# IRHapticFeedbackBoard.net
KiCad netlist of a schematic drawn in EAGLE
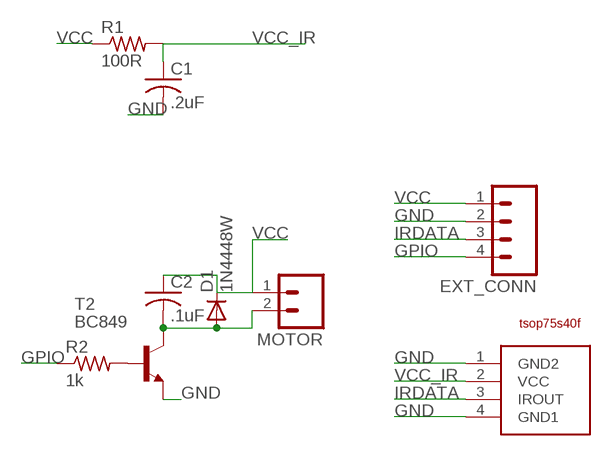
[diagram p0: schematic, sheet 1]

(export (version "E")
  (design (tool "Eeschema 10.0.6"))
  (components
    (comp (ref "C1")
      (value ".2uF")
      (footprint "eagle-import:C0603")
      (libsource (lib "eagle-import") (part "C-USC0603"))
    )
    (comp (ref "C2")
      (value ".1uF")
      (footprint "eagle-import:C0603")
      (libsource (lib "eagle-import") (part "C-USC0603"))
    )
    (comp (ref "D1")
      (value "1N4448W")
      (footprint "eagle-import:SOD-123")
      (libsource (lib "eagle-import") (part "DIODE-SOD-123"))
    )
    (comp (ref "EXT_CONN")
      (value "M04PTH")
      (footprint "eagle-import:1X04")
      (libsource (lib "eagle-import") (part "M04PTH"))
    )
    (comp (ref "MOTOR")
      (value "M02PTH")
      (footprint "eagle-import:1X02")
      (libsource (lib "eagle-import") (part "M02PTH"))
    )
    (comp (ref "R1")
      (value "100R")
      (footprint "eagle-import:R0603")
      (libsource (lib "eagle-import") (part "R-US_R0603"))
    )
    (comp (ref "R2")
      (value "1k")
      (footprint "eagle-import:R0603")
      (libsource (lib "eagle-import") (part "R-US_R0603"))
    )
    (comp (ref "T2")
      (value "BC849")
      (footprint "eagle-import:SOT23")
      (libsource (lib "eagle-import") (part "BC849"))
    )
    (comp (ref "U$1")
      (value "TSOP75S40F")
      (footprint "eagle-import:TSOP75S40F")
      (libsource (lib "eagle-import") (part "TSOP75S40F"))
    )
  )
  (nets
    (net (code "1") (name "/GND") (class "Default")
      (node (ref "C1") (pin "2") (pinfunction "2_2") (pintype "passive"))
      (node (ref "EXT_CONN") (pin "2") (pinfunction "2_2") (pintype "passive"))
      (node (ref "T2") (pin "2") (pinfunction "E_2") (pintype "passive"))
      (node (ref "U$1") (pin "1") (pinfunction "GND2_1") (pintype "bidirectional"))
      (node (ref "U$1") (pin "4") (pinfunction "GND1_4") (pintype "bidirectional"))
    )
    (net (code "2") (name "/GPIO") (class "Default")
      (node (ref "EXT_CONN") (pin "4") (pinfunction "4_4") (pintype "passive"))
      (node (ref "R2") (pin "1") (pinfunction "1_1") (pintype "passive"))
    )
    (net (code "3") (name "/IRDATA") (class "Default")
      (node (ref "EXT_CONN") (pin "3") (pinfunction "3_3") (pintype "passive"))
      (node (ref "U$1") (pin "3") (pinfunction "IROUT_3") (pintype "bidirectional"))
    )
    (net (code "4") (name "/VCC") (class "Default")
      (node (ref "C2") (pin "1") (pinfunction "1_1") (pintype "passive"))
      (node (ref "D1") (pin "C") (pinfunction "C_C") (pintype "passive"))
      (node (ref "EXT_CONN") (pin "1") (pinfunction "1_1") (pintype "passive"))
      (node (ref "MOTOR") (pin "1") (pinfunction "1_1") (pintype "passive"))
      (node (ref "R1") (pin "1") (pinfunction "1_1") (pintype "passive"))
    )
    (net (code "5") (name "/VCC_IR") (class "Default")
      (node (ref "C1") (pin "1") (pinfunction "1_1") (pintype "passive"))
      (node (ref "R1") (pin "2") (pinfunction "2_2") (pintype "passive"))
      (node (ref "U$1") (pin "2") (pinfunction "VCC_2") (pintype "bidirectional"))
    )
    (net (code "6") (name "Net-(T2-B)") (class "Default")
      (node (ref "R2") (pin "2") (pinfunction "2_2") (pintype "passive"))
      (node (ref "T2") (pin "1") (pinfunction "B_1") (pintype "passive"))
    )
    (net (code "7") (name "Net-(T2-C)") (class "Default")
      (node (ref "C2") (pin "2") (pinfunction "2_2") (pintype "passive"))
      (node (ref "D1") (pin "A") (pinfunction "A_A") (pintype "passive"))
      (node (ref "MOTOR") (pin "2") (pinfunction "2_2") (pintype "passive"))
      (node (ref "T2") (pin "3") (pinfunction "C_3") (pintype "passive"))
    )
  )
)
